# esp-module-su.net
KiCad netlist of a schematic drawn in EAGLE
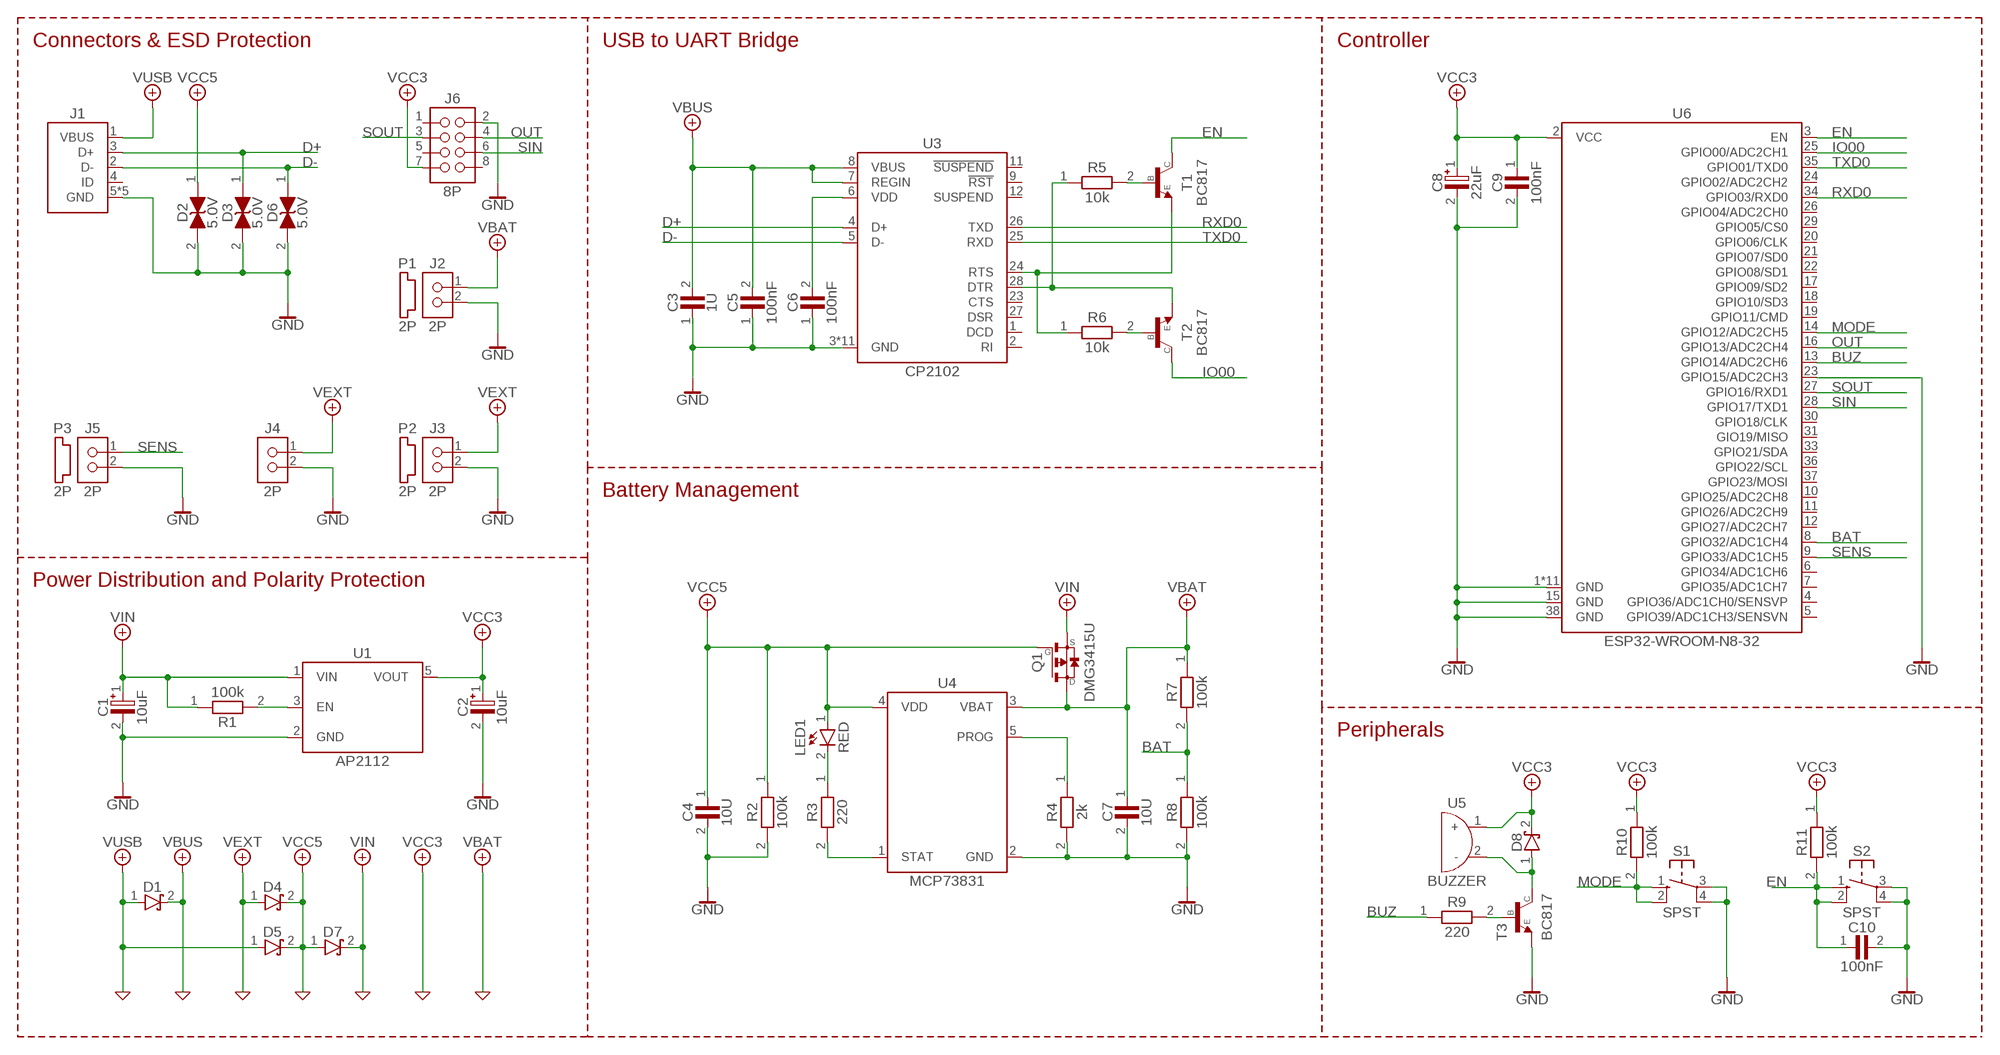
[diagram p0: schematic, sheet 1]

(export (version "E")
  (design (tool "Eeschema 10.0.6"))
  (components
    (comp (ref "C1")
      (value "10uF")
      (footprint "eagle-import:I1206-M3216-D")
      (fields
        (field (name "MF") "Kyocera AVX")
        (field (name "MPN") "TAJA106K016RNJ")
        (field (name "VOLTAGE") "16V")
      )
      (libsource (lib "eagle-import") (part "CAPACITOR-TANTALUM-I1206-M3216-10U"))
    )
    (comp (ref "C2")
      (value "10uF")
      (footprint "eagle-import:I1206-M3216-D")
      (fields
        (field (name "MF") "Kyocera AVX")
        (field (name "MPN") "TAJA106K016RNJ")
        (field (name "VOLTAGE") "16V")
      )
      (libsource (lib "eagle-import") (part "CAPACITOR-TANTALUM-I1206-M3216-10U"))
    )
    (comp (ref "C3")
      (value "1U")
      (footprint "eagle-import:I0805-M2012-C")
      (fields
        (field (name "MF") " FH (Guangdong Fenghua Advanced Tech)")
        (field (name "MPN") "0805B105K500NT")
        (field (name "TOLERANCE") "10%")
      )
      (libsource (lib "eagle-import") (part "CAPACITOR-CERAMIC-I0805-M2012-1U"))
    )
    (comp (ref "C4")
      (value "10U")
      (footprint "eagle-import:I0805-M2012-C")
      (fields
        (field (name "MF") "Samsung Electro-Mechanics")
        (field (name "MPN") "CL21A106KAYNNNE")
        (field (name "TOLERANCE") "10%")
      )
      (libsource (lib "eagle-import") (part "CAPACITOR-CERAMIC-I0805-M2012-10U"))
    )
    (comp (ref "C5")
      (value "100nF")
      (footprint "eagle-import:I0805-M2012-C")
      (fields
        (field (name "MF") "FH (Guangdong Fenghua Advanced Tech)")
        (field (name "MPN") "0805B104K500NT")
        (field (name "TOLERANCE") "10%")
      )
      (libsource (lib "eagle-import") (part "CAPACITOR-CERAMIC-I0805-M2012-100N"))
    )
    (comp (ref "C6")
      (value "100nF")
      (footprint "eagle-import:I0805-M2012-C")
      (fields
        (field (name "MF") "FH (Guangdong Fenghua Advanced Tech)")
        (field (name "MPN") "0805B104K500NT")
        (field (name "TOLERANCE") "10%")
      )
      (libsource (lib "eagle-import") (part "CAPACITOR-CERAMIC-I0805-M2012-100N"))
    )
    (comp (ref "C7")
      (value "10U")
      (footprint "eagle-import:I0805-M2012-C")
      (fields
        (field (name "MF") "Samsung Electro-Mechanics")
        (field (name "MPN") "CL21A106KAYNNNE")
        (field (name "TOLERANCE") "10%")
      )
      (libsource (lib "eagle-import") (part "CAPACITOR-CERAMIC-I0805-M2012-10U"))
    )
    (comp (ref "C8")
      (value "22uF")
      (footprint "eagle-import:I1206-M3216-D")
      (fields
        (field (name "MF") "Kyocera AVX")
        (field (name "MPN") "TAJA226K010RNJ")
        (field (name "VOLTAGE") "10V")
      )
      (libsource (lib "eagle-import") (part "CAPACITOR-TANTALUM-I1206-M3216-22U"))
    )
    (comp (ref "C9")
      (value "100nF")
      (footprint "eagle-import:I0805-M2012-C")
      (fields
        (field (name "MF") "FH (Guangdong Fenghua Advanced Tech)")
        (field (name "MPN") "0805B104K500NT")
        (field (name "TOLERANCE") "10%")
      )
      (libsource (lib "eagle-import") (part "CAPACITOR-CERAMIC-I0805-M2012-100N"))
    )
    (comp (ref "C10")
      (value "100nF")
      (footprint "eagle-import:I0805-M2012-C")
      (fields
        (field (name "MF") "FH (Guangdong Fenghua Advanced Tech)")
        (field (name "MPN") "0805B104K500NT")
        (field (name "TOLERANCE") "10%")
      )
      (libsource (lib "eagle-import") (part "CAPACITOR-CERAMIC-I0805-M2012-100N"))
    )
    (comp (ref "D1")
      (value "30V")
      (footprint "eagle-import:SOD-323")
      (fields (field (name "MF") "Diodes Incorporated") (field (name "MPN") "BAT760-7"))
      (libsource (lib "eagle-import") (part "SCHOTTKY-SOD-323-30V"))
    )
    (comp (ref "D2")
      (value "5.0V")
      (footprint "eagle-import:SOD-523")
      (fields (field (name "MF") " LRC") (field (name "MPN") "LESD5D5.0CT1G"))
      (libsource (lib "eagle-import") (part "ZENER-BI-SOD-523-5.0V"))
    )
    (comp (ref "D3")
      (value "5.0V")
      (footprint "eagle-import:SOD-523")
      (fields (field (name "MF") " LRC") (field (name "MPN") "LESD5D5.0CT1G"))
      (libsource (lib "eagle-import") (part "ZENER-BI-SOD-523-5.0V"))
    )
    (comp (ref "D4")
      (value "30V")
      (footprint "eagle-import:SOD-323")
      (fields (field (name "MF") "Diodes Incorporated") (field (name "MPN") "BAT760-7"))
      (libsource (lib "eagle-import") (part "SCHOTTKY-SOD-323-30V"))
    )
    (comp (ref "D5")
      (value "30V")
      (footprint "eagle-import:SOD-323")
      (fields (field (name "MF") "Diodes Incorporated") (field (name "MPN") "BAT760-7"))
      (libsource (lib "eagle-import") (part "SCHOTTKY-SOD-323-30V"))
    )
    (comp (ref "D6")
      (value "5.0V")
      (footprint "eagle-import:SOD-523")
      (fields (field (name "MF") " LRC") (field (name "MPN") "LESD5D5.0CT1G"))
      (libsource (lib "eagle-import") (part "ZENER-BI-SOD-523-5.0V"))
    )
    (comp (ref "D7")
      (value "30V")
      (footprint "eagle-import:SOD-323")
      (fields (field (name "MF") "Diodes Incorporated") (field (name "MPN") "BAT760-7"))
      (libsource (lib "eagle-import") (part "SCHOTTKY-SOD-323-30V"))
    )
    (comp (ref "D8")
      (value "30V")
      (footprint "eagle-import:SOD-323")
      (fields (field (name "MF") "Diodes Incorporated") (field (name "MPN") "BAT760-7"))
      (libsource (lib "eagle-import") (part "SCHOTTKY-SOD-323-30V"))
    )
    (comp (ref "J1")
      (value "USB-A-MICRO-SMD-SIDE")
      (footprint "eagle-import:USB-A-MICRO-SMD-SIDE")
      (fields (field (name "MF") "XKB Connectivity") (field (name "MPN") "U254-051T-4BHJ25-F2S"))
      (libsource (lib "eagle-import") (part "USB-A-MICRO-SMD-SIDE"))
    )
    (comp (ref "J2")
      (value "2P")
      (footprint "eagle-import:JST-S2B-PH-SM4-TB")
      (fields (field (name "MF") "JST Sales America") (field (name "MPN") "S2B-PH-SM4-TB(LF)(SN)"))
      (libsource (lib "eagle-import") (part "HEADER-02P-1R-S2B-PH-SM4-TB"))
    )
    (comp (ref "J3")
      (value "2P")
      (footprint "eagle-import:JST-S2B-PH-SM4-TB")
      (fields (field (name "MF") "JST Sales America") (field (name "MPN") "S2B-PH-SM4-TB(LF)(SN)"))
      (libsource (lib "eagle-import") (part "HEADER-02P-1R-S2B-PH-SM4-TB"))
    )
    (comp (ref "J4")
      (value "2P")
      (footprint "eagle-import:PZ254V-11-02P")
      (fields (field (name "MF") " XFCN") (field (name "MPN") " PZ254V-11-02P"))
      (libsource (lib "eagle-import") (part "HEADER-02P-1R-PZ254V-11-02P"))
    )
    (comp (ref "J5")
      (value "2P")
      (footprint "eagle-import:JST-S2B-PH-SM4-TB")
      (fields (field (name "MF") "JST Sales America") (field (name "MPN") "S2B-PH-SM4-TB(LF)(SN)"))
      (libsource (lib "eagle-import") (part "HEADER-02P-1R-S2B-PH-SM4-TB"))
    )
    (comp (ref "J6")
      (value "8P")
      (footprint "eagle-import:PM254V-12-08-H85")
      (fields (field (name "MF") "XFCN") (field (name "MPN") "PM254V-12-08-H85"))
      (libsource (lib "eagle-import") (part "HEADER-08P-2R-PM254V-12-08-H85"))
    )
    (comp (ref "LED1")
      (value "RED")
      (footprint "eagle-import:I0805-M2012-D")
      (fields (field (name "MF") "Foshan NationStar Optoelectronics") (field (name "MPN") "FC-2012HRK-620D"))
      (libsource (lib "eagle-import") (part "LED-I0805-M2012-RED"))
    )
    (comp (ref "P1")
      (value "2P")
      (footprint "eagle-import:CONNECTOR-DEFAULT")
      (fields (field (name "MF") "JST Sales America") (field (name "MPN") "PHR-2"))
      (libsource (lib "eagle-import") (part "CONNECTOR-02P-1R-PHR"))
    )
    (comp (ref "P2")
      (value "2P")
      (footprint "eagle-import:CONNECTOR-DEFAULT")
      (fields (field (name "MF") "JST Sales America") (field (name "MPN") "PHR-2"))
      (libsource (lib "eagle-import") (part "CONNECTOR-02P-1R-PHR"))
    )
    (comp (ref "P3")
      (value "2P")
      (footprint "eagle-import:CONNECTOR-DEFAULT")
      (fields (field (name "MF") "JST Sales America") (field (name "MPN") "PHR-2"))
      (libsource (lib "eagle-import") (part "CONNECTOR-02P-1R-PHR"))
    )
    (comp (ref "Q1")
      (value "DMG3415U")
      (footprint "eagle-import:SOT-23-3")
      (fields
        (field (name "MF") "Diodes Incorporated")
        (field (name "MPN") "DMG3415U-7")
        (field (name "VOLTAGE") "20V")
      )
      (libsource (lib "eagle-import") (part "MOSFET-P-CHANNEL-SOT-23-3-20V-4A"))
    )
    (comp (ref "R1")
      (value "100k")
      (footprint "eagle-import:I0805-M2012-R")
      (fields (field (name "MF") "UNI-ROYAL(Uniroyal Elec)") (field (name "MPN") "0805W8F1003T5E"))
      (libsource (lib "eagle-import") (part "RESISTOR-I0805-M2012-100K"))
    )
    (comp (ref "R2")
      (value "100k")
      (footprint "eagle-import:I0805-M2012-R")
      (fields (field (name "MF") "UNI-ROYAL(Uniroyal Elec)") (field (name "MPN") "0805W8F1003T5E"))
      (libsource (lib "eagle-import") (part "RESISTOR-I0805-M2012-100K"))
    )
    (comp (ref "R3")
      (value "220")
      (footprint "eagle-import:I0805-M2012-R")
      (fields (field (name "MF") "UNI-ROYAL(Uniroyal Elec)") (field (name "MPN") "0805W8F2200T5E"))
      (libsource (lib "eagle-import") (part "RESISTOR-I0805-M2012-220"))
    )
    (comp (ref "R4")
      (value "2k")
      (footprint "eagle-import:I0805-M2012-R")
      (fields (field (name "MF") "UNI-ROYAL(Uniroyal Elec)") (field (name "MPN") "0805W8F2001T5E"))
      (libsource (lib "eagle-import") (part "RESISTOR-I0805-M2012-2K"))
    )
    (comp (ref "R5")
      (value "10k")
      (footprint "eagle-import:I0805-M2012-R")
      (fields (field (name "MF") " UNI-ROYAL(Uniroyal Elec)") (field (name "MPN") "0805W8F1002T5E"))
      (libsource (lib "eagle-import") (part "RESISTOR-I0805-M2012-10K"))
    )
    (comp (ref "R6")
      (value "10k")
      (footprint "eagle-import:I0805-M2012-R")
      (fields (field (name "MF") " UNI-ROYAL(Uniroyal Elec)") (field (name "MPN") "0805W8F1002T5E"))
      (libsource (lib "eagle-import") (part "RESISTOR-I0805-M2012-10K"))
    )
    (comp (ref "R7")
      (value "100k")
      (footprint "eagle-import:I0805-M2012-R")
      (fields (field (name "MF") "UNI-ROYAL(Uniroyal Elec)") (field (name "MPN") "0805W8F1003T5E"))
      (libsource (lib "eagle-import") (part "RESISTOR-I0805-M2012-100K"))
    )
    (comp (ref "R8")
      (value "100k")
      (footprint "eagle-import:I0805-M2012-R")
      (fields (field (name "MF") "UNI-ROYAL(Uniroyal Elec)") (field (name "MPN") "0805W8F1003T5E"))
      (libsource (lib "eagle-import") (part "RESISTOR-I0805-M2012-100K"))
    )
    (comp (ref "R9")
      (value "220")
      (footprint "eagle-import:I0805-M2012-R")
      (fields (field (name "MF") "UNI-ROYAL(Uniroyal Elec)") (field (name "MPN") "0805W8F2200T5E"))
      (libsource (lib "eagle-import") (part "RESISTOR-I0805-M2012-220"))
    )
    (comp (ref "R10")
      (value "100k")
      (footprint "eagle-import:I0805-M2012-R")
      (fields (field (name "MF") "UNI-ROYAL(Uniroyal Elec)") (field (name "MPN") "0805W8F1003T5E"))
      (libsource (lib "eagle-import") (part "RESISTOR-I0805-M2012-100K"))
    )
    (comp (ref "R11")
      (value "100k")
      (footprint "eagle-import:I0805-M2012-R")
      (fields (field (name "MF") "UNI-ROYAL(Uniroyal Elec)") (field (name "MPN") "0805W8F1003T5E"))
      (libsource (lib "eagle-import") (part "RESISTOR-I0805-M2012-100K"))
    )
    (comp (ref "S1")
      (value "SPST")
      (footprint "eagle-import:SMD-SW-4")
      (fields
        (field (name "MF") "XKB Enterprise")
        (field (name "MPN") "TS-1187A-B-A-B")
        (field (name "VOLTAGE") "12V")
      )
      (libsource (lib "eagle-import") (part "SWITCH-12V-50MA"))
    )
    (comp (ref "S2")
      (value "SPST")
      (footprint "eagle-import:SMD-SW-4")
      (fields
        (field (name "MF") "XKB Enterprise")
        (field (name "MPN") "TS-1187A-B-A-B")
        (field (name "VOLTAGE") "12V")
      )
      (libsource (lib "eagle-import") (part "SWITCH-12V-50MA"))
    )
    (comp (ref "T1")
      (value "BC817")
      (footprint "eagle-import:SOT-23-3")
      (fields (field (name "MF") " Nexperia") (field (name "MPN") " BC817-40,215"))
      (libsource (lib "eagle-import") (part "TRANSISTOR-NPN-SOT-23-3"))
    )
    (comp (ref "T2")
      (value "BC817")
      (footprint "eagle-import:SOT-23-3")
      (fields (field (name "MF") " Nexperia") (field (name "MPN") " BC817-40,215"))
      (libsource (lib "eagle-import") (part "TRANSISTOR-NPN-SOT-23-3"))
    )
    (comp (ref "T3")
      (value "BC817")
      (footprint "eagle-import:SOT-23-3")
      (fields (field (name "MF") " Nexperia") (field (name "MPN") " BC817-40,215"))
      (libsource (lib "eagle-import") (part "TRANSISTOR-NPN-SOT-23-3"))
    )
    (comp (ref "U1")
      (value "AP2112")
      (footprint "eagle-import:SOT-25-5")
      (fields (field (name "MF") "TECH PUBLIC") (field (name "MPN") "TPAP2112K-3.3TRG1"))
      (libsource (lib "eagle-import") (part "AP2112-SOT-25-5"))
    )
    (comp (ref "U3")
      (value "CP2102")
      (footprint "eagle-import:QFN-28")
      (fields (field (name "MF") "SILICON LABS") (field (name "MPN") "CP2102-GMR"))
      (libsource (lib "eagle-import") (part "CP2102-QFN-28"))
    )
    (comp (ref "U4")
      (value "MCP73831")
      (footprint "eagle-import:SOT-23-5")
      (fields (field (name "MF") "Microchip Tech") (field (name "MPN") "MCP73831T-2ATI/OT"))
      (libsource (lib "eagle-import") (part "MCP73831-SOT-23-5"))
    )
    (comp (ref "U5")
      (value "BUZZER")
      (footprint "eagle-import:SMD-BUZZER")
      (fields (field (name "MF") "MLT-7525") (field (name "MPN") "Jiangsu Huaneng Elec"))
      (libsource (lib "eagle-import") (part "BUZZER"))
    )
    (comp (ref "U6")
      (value "ESP32-WROOM-N8-32")
      (footprint "eagle-import:ESP32-WROOM-32")
      (fields (field (name "MF") "Espressif Systems") (field (name "MPN") " ESP32-WROOM-32-N8"))
      (libsource (lib "eagle-import") (part "ESP32-WROOM-32-N8"))
    )
  )
  (nets
    (net (code "1") (name "/BAT") (class "Default")
      (node (ref "R7") (pin "2") (pinfunction "2_2") (pintype "passive"))
      (node (ref "R8") (pin "1") (pinfunction "1_1") (pintype "passive"))
      (node (ref "U6") (pin "8") (pinfunction "GPIO32/ADC1CH4_8") (pintype "bidirectional"))
    )
    (net (code "2") (name "/BUZ") (class "Default")
      (node (ref "R9") (pin "1") (pinfunction "1_1") (pintype "passive"))
      (node (ref "U6") (pin "13") (pinfunction "GPIO14/ADC2CH6_13") (pintype "bidirectional"))
    )
    (net (code "3") (name "/D+") (class "Default")
      (node (ref "D3") (pin "1") (pinfunction "A_1") (pintype "passive"))
      (node (ref "J1") (pin "3") (pinfunction "D+_3") (pintype "bidirectional"))
      (node (ref "U3") (pin "4") (pinfunction "D+_4") (pintype "bidirectional"))
    )
    (net (code "4") (name "/D-") (class "Default")
      (node (ref "D6") (pin "1") (pinfunction "A_1") (pintype "passive"))
      (node (ref "J1") (pin "2") (pinfunction "D-_2") (pintype "bidirectional"))
      (node (ref "U3") (pin "5") (pinfunction "D-_5") (pintype "bidirectional"))
    )
    (net (code "5") (name "/EN") (class "Default")
      (node (ref "C10") (pin "1") (pinfunction "1_1") (pintype "passive"))
      (node (ref "R11") (pin "2") (pinfunction "2_2") (pintype "passive"))
      (node (ref "S2") (pin "1") (pinfunction "1_1") (pintype "bidirectional"))
      (node (ref "S2") (pin "2") (pinfunction "2_2") (pintype "bidirectional"))
      (node (ref "T1") (pin "3") (pinfunction "C_3") (pintype "passive"))
      (node (ref "U6") (pin "3") (pinfunction "EN_3") (pintype "bidirectional"))
    )
    (net (code "6") (name "/IO00") (class "Default")
      (node (ref "T2") (pin "3") (pinfunction "C_3") (pintype "passive"))
      (node (ref "U6") (pin "25") (pinfunction "GPIO00/ADC2CH1_25") (pintype "bidirectional"))
    )
    (net (code "7") (name "/MODE") (class "Default")
      (node (ref "R10") (pin "2") (pinfunction "2_2") (pintype "passive"))
      (node (ref "S1") (pin "1") (pinfunction "1_1") (pintype "bidirectional"))
      (node (ref "S1") (pin "2") (pinfunction "2_2") (pintype "bidirectional"))
      (node (ref "U6") (pin "14") (pinfunction "GPIO12/ADC2CH5_14") (pintype "bidirectional"))
    )
    (net (code "8") (name "/OUT") (class "Default")
      (node (ref "J6") (pin "4") (pinfunction "04_4") (pintype "passive"))
      (node (ref "U6") (pin "16") (pinfunction "GPIO13/ADC2CH4_16") (pintype "bidirectional"))
    )
    (net (code "9") (name "/RXD0") (class "Default")
      (node (ref "U3") (pin "26") (pinfunction "TXD_26") (pintype "bidirectional"))
      (node (ref "U6") (pin "34") (pinfunction "GPIO03/RXD0_34") (pintype "bidirectional"))
    )
    (net (code "10") (name "/SENS") (class "Default")
      (node (ref "J5") (pin "1") (pinfunction "01_1") (pintype "passive"))
      (node (ref "U6") (pin "9") (pinfunction "GPIO33/ADC1CH5_9") (pintype "bidirectional"))
    )
    (net (code "11") (name "/SIN") (class "Default")
      (node (ref "J6") (pin "6") (pinfunction "06_6") (pintype "passive"))
      (node (ref "U6") (pin "28") (pinfunction "GPIO17/TXD1_28") (pintype "bidirectional"))
    )
    (net (code "12") (name "/SOUT") (class "Default")
      (node (ref "J6") (pin "3") (pinfunction "03_3") (pintype "passive"))
      (node (ref "U6") (pin "27") (pinfunction "GPIO16/RXD1_27") (pintype "bidirectional"))
    )
    (net (code "13") (name "/TXD0") (class "Default")
      (node (ref "U3") (pin "25") (pinfunction "RXD_25") (pintype "bidirectional"))
      (node (ref "U6") (pin "35") (pinfunction "GPIO01/TXD0_35") (pintype "bidirectional"))
    )
    (net (code "14") (name "GND") (class "Default")
      (node (ref "C1") (pin "2") (pinfunction "-_2") (pintype "passive"))
      (node (ref "C10") (pin "2") (pinfunction "2_2") (pintype "passive"))
      (node (ref "C2") (pin "2") (pinfunction "-_2") (pintype "passive"))
      (node (ref "C3") (pin "1") (pinfunction "1_1") (pintype "passive"))
      (node (ref "C4") (pin "2") (pinfunction "2_2") (pintype "passive"))
      (node (ref "C5") (pin "1") (pinfunction "1_1") (pintype "passive"))
      (node (ref "C6") (pin "1") (pinfunction "1_1") (pintype "passive"))
      (node (ref "C7") (pin "2") (pinfunction "2_2") (pintype "passive"))
      (node (ref "C8") (pin "2") (pinfunction "-_2") (pintype "passive"))
      (node (ref "C9") (pin "2") (pinfunction "2_2") (pintype "passive"))
      (node (ref "D2") (pin "2") (pinfunction "C_2") (pintype "passive"))
      (node (ref "D3") (pin "2") (pinfunction "C_2") (pintype "passive"))
      (node (ref "D6") (pin "2") (pinfunction "C_2") (pintype "passive"))
      (node (ref "J1") (pin "5") (pinfunction "GND_5") (pintype "power_in"))
      (node (ref "J1") (pin "6") (pinfunction "GND_6") (pintype "power_in"))
      (node (ref "J1") (pin "7") (pinfunction "GND_7") (pintype "power_in"))
      (node (ref "J1") (pin "8") (pinfunction "GND_8") (pintype "power_in"))
      (node (ref "J1") (pin "9") (pinfunction "GND_9") (pintype "power_in"))
      (node (ref "J2") (pin "2") (pinfunction "02_2") (pintype "passive"))
      (node (ref "J3") (pin "2") (pinfunction "02_2") (pintype "passive"))
      (node (ref "J4") (pin "2") (pinfunction "02_2") (pintype "passive"))
      (node (ref "J5") (pin "2") (pinfunction "02_2") (pintype "passive"))
      (node (ref "J6") (pin "2") (pinfunction "02_2") (pintype "passive"))
      (node (ref "R2") (pin "2") (pinfunction "2_2") (pintype "passive"))
      (node (ref "R4") (pin "2") (pinfunction "2_2") (pintype "passive"))
      (node (ref "R8") (pin "2") (pinfunction "2_2") (pintype "passive"))
      (node (ref "S1") (pin "3") (pinfunction "3_3") (pintype "bidirectional"))
      (node (ref "S1") (pin "4") (pinfunction "4_4") (pintype "bidirectional"))
      (node (ref "S2") (pin "3") (pinfunction "3_3") (pintype "bidirectional"))
      (node (ref "S2") (pin "4") (pinfunction "4_4") (pintype "bidirectional"))
      (node (ref "T3") (pin "2") (pinfunction "E_2") (pintype "passive"))
      (node (ref "U1") (pin "2") (pinfunction "GND_2") (pintype "power_in"))
      (node (ref "U3") (pin "29") (pinfunction "GND_29") (pintype "power_in"))
      (node (ref "U3") (pin "3") (pinfunction "GND_3") (pintype "power_in"))
      (node (ref "U3") (pin "30") (pinfunction "GND_30") (pintype "power_in"))
      (node (ref "U3") (pin "31") (pinfunction "GND_31") (pintype "power_in"))
      (node (ref "U3") (pin "32") (pinfunction "GND_32") (pintype "power_in"))
      (node (ref "U3") (pin "33") (pinfunction "GND_33") (pintype "power_in"))
      (node (ref "U3") (pin "34") (pinfunction "GND_34") (pintype "power_in"))
      (node (ref "U3") (pin "35") (pinfunction "GND_35") (pintype "power_in"))
      (node (ref "U3") (pin "36") (pinfunction "GND_36") (pintype "power_in"))
      (node (ref "U3") (pin "37") (pinfunction "GND_37") (pintype "power_in"))
      (node (ref "U3") (pin "38") (pinfunction "GND_38") (pintype "power_in"))
      (node (ref "U4") (pin "2") (pinfunction "GND_2") (pintype "power_in"))
      (node (ref "U6") (pin "1") (pinfunction "GND_1") (pintype "power_in"))
      (node (ref "U6") (pin "15") (pinfunction "GND_15") (pintype "power_in"))
      (node (ref "U6") (pin "23") (pinfunction "GPIO15/ADC2CH3_23") (pintype "bidirectional"))
      (node (ref "U6") (pin "38") (pinfunction "GND_38") (pintype "bidirectional"))
      (node (ref "U6") (pin "39") (pinfunction "GND_39") (pintype "power_in"))
      (node (ref "U6") (pin "40") (pinfunction "GND_40") (pintype "power_in"))
      (node (ref "U6") (pin "41") (pinfunction "GND_41") (pintype "power_in"))
      (node (ref "U6") (pin "42") (pinfunction "GND_42") (pintype "power_in"))
      (node (ref "U6") (pin "43") (pinfunction "GND_43") (pintype "power_in"))
      (node (ref "U6") (pin "44") (pinfunction "GND_44") (pintype "power_in"))
      (node (ref "U6") (pin "45") (pinfunction "GND_45") (pintype "power_in"))
      (node (ref "U6") (pin "46") (pinfunction "GND_46") (pintype "power_in"))
      (node (ref "U6") (pin "47") (pinfunction "GND_47") (pintype "power_in"))
      (node (ref "U6") (pin "48") (pinfunction "GND_48") (pintype "power_in"))
    )
    (net (code "15") (name "Net-(D8-A)") (class "Default")
      (node (ref "D8") (pin "1") (pinfunction "A_1") (pintype "passive"))
      (node (ref "T3") (pin "3") (pinfunction "C_3") (pintype "passive"))
      (node (ref "U5") (pin "2") (pinfunction "-_2") (pintype "bidirectional"))
    )
    (net (code "16") (name "Net-(LED1-C)") (class "Default")
      (node (ref "LED1") (pin "2") (pinfunction "C_2") (pintype "passive"))
      (node (ref "R3") (pin "1") (pinfunction "1_1") (pintype "passive"))
    )
    (net (code "17") (name "Net-(T1-B)") (class "Default")
      (node (ref "R5") (pin "2") (pinfunction "2_2") (pintype "passive"))
      (node (ref "T1") (pin "1") (pinfunction "B_1") (pintype "passive"))
    )
    (net (code "18") (name "Net-(T1-E)") (class "Default")
      (node (ref "R6") (pin "1") (pinfunction "1_1") (pintype "passive"))
      (node (ref "T1") (pin "2") (pinfunction "E_2") (pintype "passive"))
      (node (ref "U3") (pin "24") (pinfunction "RTS_24") (pintype "bidirectional"))
    )
    (net (code "19") (name "Net-(T2-B)") (class "Default")
      (node (ref "R6") (pin "2") (pinfunction "2_2") (pintype "passive"))
      (node (ref "T2") (pin "1") (pinfunction "B_1") (pintype "passive"))
    )
    (net (code "20") (name "Net-(T2-E)") (class "Default")
      (node (ref "R5") (pin "1") (pinfunction "1_1") (pintype "passive"))
      (node (ref "T2") (pin "2") (pinfunction "E_2") (pintype "passive"))
      (node (ref "U3") (pin "28") (pinfunction "DTR_28") (pintype "bidirectional"))
    )
    (net (code "21") (name "Net-(T3-B)") (class "Default")
      (node (ref "R9") (pin "2") (pinfunction "2_2") (pintype "passive"))
      (node (ref "T3") (pin "1") (pinfunction "B_1") (pintype "passive"))
    )
    (net (code "22") (name "Net-(U1-EN)") (class "Default")
      (node (ref "R1") (pin "2") (pinfunction "2_2") (pintype "passive"))
      (node (ref "U1") (pin "3") (pinfunction "EN_3") (pintype "bidirectional"))
    )
    (net (code "23") (name "Net-(U3-VDD)") (class "Default")
      (node (ref "C6") (pin "2") (pinfunction "2_2") (pintype "passive"))
      (node (ref "U3") (pin "6") (pinfunction "VDD_6") (pintype "power_in"))
    )
    (net (code "24") (name "Net-(U4-PROG)") (class "Default")
      (node (ref "R4") (pin "1") (pinfunction "1_1") (pintype "passive"))
      (node (ref "U4") (pin "5") (pinfunction "PROG_5") (pintype "bidirectional"))
    )
    (net (code "25") (name "Net-(U4-STAT)") (class "Default")
      (node (ref "R3") (pin "2") (pinfunction "2_2") (pintype "passive"))
      (node (ref "U4") (pin "1") (pinfunction "STAT_1") (pintype "bidirectional"))
    )
    (net (code "26") (name "VBAT") (class "Default")
      (node (ref "C7") (pin "1") (pinfunction "1_1") (pintype "passive"))
      (node (ref "J2") (pin "1") (pinfunction "01_1") (pintype "passive"))
      (node (ref "Q1") (pin "3") (pinfunction "D_3") (pintype "passive"))
      (node (ref "R7") (pin "1") (pinfunction "1_1") (pintype "passive"))
      (node (ref "U4") (pin "3") (pinfunction "VBAT_3") (pintype "bidirectional"))
    )
    (net (code "27") (name "VBUS") (class "Default")
      (node (ref "C3") (pin "2") (pinfunction "2_2") (pintype "passive"))
      (node (ref "C5") (pin "2") (pinfunction "2_2") (pintype "passive"))
      (node (ref "D1") (pin "2") (pinfunction "C_2") (pintype "passive"))
      (node (ref "U3") (pin "7") (pinfunction "REGIN_7") (pintype "bidirectional"))
      (node (ref "U3") (pin "8") (pinfunction "VBUS_8") (pintype "bidirectional"))
    )
    (net (code "28") (name "VCC3") (class "Default")
      (node (ref "C2") (pin "1") (pinfunction "+_1") (pintype "passive"))
      (node (ref "C8") (pin "1") (pinfunction "+_1") (pintype "passive"))
      (node (ref "C9") (pin "1") (pinfunction "1_1") (pintype "passive"))
      (node (ref "D8") (pin "2") (pinfunction "C_2") (pintype "passive"))
      (node (ref "J6") (pin "7") (pinfunction "07_7") (pintype "passive"))
      (node (ref "R10") (pin "1") (pinfunction "1_1") (pintype "passive"))
      (node (ref "R11") (pin "1") (pinfunction "1_1") (pintype "passive"))
      (node (ref "U1") (pin "5") (pinfunction "VOUT_5") (pintype "power_in"))
      (node (ref "U5") (pin "1") (pinfunction "+_1") (pintype "bidirectional"))
      (node (ref "U6") (pin "2") (pinfunction "VCC_2") (pintype "power_in"))
    )
    (net (code "29") (name "VCC5") (class "Default")
      (node (ref "C4") (pin "1") (pinfunction "1_1") (pintype "passive"))
      (node (ref "D2") (pin "1") (pinfunction "A_1") (pintype "passive"))
      (node (ref "D4") (pin "2") (pinfunction "C_2") (pintype "passive"))
      (node (ref "D5") (pin "2") (pinfunction "C_2") (pintype "passive"))
      (node (ref "D7") (pin "1") (pinfunction "A_1") (pintype "passive"))
      (node (ref "LED1") (pin "1") (pinfunction "A_1") (pintype "passive"))
      (node (ref "Q1") (pin "1") (pinfunction "G_1") (pintype "passive"))
      (node (ref "R2") (pin "1") (pinfunction "1_1") (pintype "passive"))
      (node (ref "U4") (pin "4") (pinfunction "VDD_4") (pintype "power_in"))
    )
    (net (code "30") (name "VEXT") (class "Default")
      (node (ref "D4") (pin "1") (pinfunction "A_1") (pintype "passive"))
      (node (ref "J3") (pin "1") (pinfunction "01_1") (pintype "passive"))
      (node (ref "J4") (pin "1") (pinfunction "01_1") (pintype "passive"))
    )
    (net (code "31") (name "VIN") (class "Default")
      (node (ref "C1") (pin "1") (pinfunction "+_1") (pintype "passive"))
      (node (ref "D7") (pin "2") (pinfunction "C_2") (pintype "passive"))
      (node (ref "Q1") (pin "2") (pinfunction "S_2") (pintype "passive"))
      (node (ref "R1") (pin "1") (pinfunction "1_1") (pintype "passive"))
      (node (ref "U1") (pin "1") (pinfunction "VIN_1") (pintype "power_in"))
    )
    (net (code "32") (name "VUSB") (class "Default")
      (node (ref "D1") (pin "1") (pinfunction "A_1") (pintype "passive"))
      (node (ref "D5") (pin "1") (pinfunction "A_1") (pintype "passive"))
      (node (ref "J1") (pin "1") (pinfunction "VBUS_1") (pintype "power_in"))
    )
    (net (code "33") (name "unconnected-(J1-ID-Pad4)") (class "Default")
      (node (ref "J1") (pin "4") (pinfunction "ID_4") (pintype "passive"))
    )
    (net (code "34") (name "unconnected-(J6-01-Pad1)") (class "Default")
      (node (ref "J6") (pin "1") (pinfunction "01_1") (pintype "passive"))
    )
    (net (code "35") (name "unconnected-(J6-05-Pad5)") (class "Default")
      (node (ref "J6") (pin "5") (pinfunction "05_5") (pintype "passive"))
    )
    (net (code "36") (name "unconnected-(J6-08-Pad8)") (class "Default")
      (node (ref "J6") (pin "8") (pinfunction "08_8") (pintype "passive"))
    )
    (net (code "37") (name "unconnected-(U3-CTS-Pad23)") (class "Default")
      (node (ref "U3") (pin "23") (pinfunction "CTS_23") (pintype "bidirectional"))
    )
    (net (code "38") (name "unconnected-(U3-DCD-Pad1)") (class "Default")
      (node (ref "U3") (pin "1") (pinfunction "DCD_1") (pintype "bidirectional"))
    )
    (net (code "39") (name "unconnected-(U3-DSR-Pad27)") (class "Default")
      (node (ref "U3") (pin "27") (pinfunction "DSR_27") (pintype "bidirectional"))
    )
    (net (code "40") (name "unconnected-(U3-RI-Pad2)") (class "Default")
      (node (ref "U3") (pin "2") (pinfunction "RI_2") (pintype "bidirectional"))
    )
    (net (code "41") (name "unconnected-(U3-SUSPEND-Pad12)") (class "Default")
      (node (ref "U3") (pin "12") (pinfunction "SUSPEND_12") (pintype "bidirectional"))
    )
    (net (code "42") (name "unconnected-(U3-~{RST}-Pad9)") (class "Default")
      (node (ref "U3") (pin "9") (pinfunction "~{RST}_9") (pintype "bidirectional"))
    )
    (net (code "43") (name "unconnected-(U3-~{SUSPEND}-Pad11)") (class "Default")
      (node (ref "U3") (pin "11") (pinfunction "~{SUSPEND}_11") (pintype "bidirectional"))
    )
    (net (code "44") (name "unconnected-(U6-GIO19{slash}MISO-Pad31)") (class "Default")
      (node (ref "U6") (pin "31") (pinfunction "GIO19/MISO_31") (pintype "bidirectional"))
    )
    (net (code "45") (name "unconnected-(U6-GPIO02{slash}ADC2CH2-Pad24)") (class "Default")
      (node (ref "U6") (pin "24") (pinfunction "GPIO02/ADC2CH2_24") (pintype "bidirectional"))
    )
    (net (code "46") (name "unconnected-(U6-GPIO04{slash}ADC2CH0-Pad26)") (class "Default")
      (node (ref "U6") (pin "26") (pinfunction "GPIO04/ADC2CH0_26") (pintype "bidirectional"))
    )
    (net (code "47") (name "unconnected-(U6-GPIO05{slash}CS0-Pad29)") (class "Default")
      (node (ref "U6") (pin "29") (pinfunction "GPIO05/CS0_29") (pintype "bidirectional"))
    )
    (net (code "48") (name "unconnected-(U6-GPIO06{slash}CLK-Pad20)") (class "Default")
      (node (ref "U6") (pin "20") (pinfunction "GPIO06/CLK_20") (pintype "bidirectional"))
    )
    (net (code "49") (name "unconnected-(U6-GPIO07{slash}SD0-Pad21)") (class "Default")
      (node (ref "U6") (pin "21") (pinfunction "GPIO07/SD0_21") (pintype "bidirectional"))
    )
    (net (code "50") (name "unconnected-(U6-GPIO08{slash}SD1-Pad22)") (class "Default")
      (node (ref "U6") (pin "22") (pinfunction "GPIO08/SD1_22") (pintype "bidirectional"))
    )
    (net (code "51") (name "unconnected-(U6-GPIO09{slash}SD2-Pad17)") (class "Default")
      (node (ref "U6") (pin "17") (pinfunction "GPIO09/SD2_17") (pintype "bidirectional"))
    )
    (net (code "52") (name "unconnected-(U6-GPIO10{slash}SD3-Pad18)") (class "Default")
      (node (ref "U6") (pin "18") (pinfunction "GPIO10/SD3_18") (pintype "bidirectional"))
    )
    (net (code "53") (name "unconnected-(U6-GPIO11{slash}CMD-Pad19)") (class "Default")
      (node (ref "U6") (pin "19") (pinfunction "GPIO11/CMD_19") (pintype "bidirectional"))
    )
    (net (code "54") (name "unconnected-(U6-GPIO18{slash}CLK-Pad30)") (class "Default")
      (node (ref "U6") (pin "30") (pinfunction "GPIO18/CLK_30") (pintype "bidirectional"))
    )
    (net (code "55") (name "unconnected-(U6-GPIO21{slash}SDA-Pad33)") (class "Default")
      (node (ref "U6") (pin "33") (pinfunction "GPIO21/SDA_33") (pintype "bidirectional"))
    )
    (net (code "56") (name "unconnected-(U6-GPIO22{slash}SCL-Pad36)") (class "Default")
      (node (ref "U6") (pin "36") (pinfunction "GPIO22/SCL_36") (pintype "bidirectional"))
    )
    (net (code "57") (name "unconnected-(U6-GPIO23{slash}MOSI-Pad37)") (class "Default")
      (node (ref "U6") (pin "37") (pinfunction "GPIO23/MOSI_37") (pintype "bidirectional"))
    )
    (net (code "58") (name "unconnected-(U6-GPIO25{slash}ADC2CH8-Pad10)") (class "Default")
      (node (ref "U6") (pin "10") (pinfunction "GPIO25/ADC2CH8_10") (pintype "bidirectional"))
    )
    (net (code "59") (name "unconnected-(U6-GPIO26{slash}ADC2CH9-Pad11)") (class "Default")
      (node (ref "U6") (pin "11") (pinfunction "GPIO26/ADC2CH9_11") (pintype "bidirectional"))
    )
    (net (code "60") (name "unconnected-(U6-GPIO27{slash}ADC2CH7-Pad12)") (class "Default")
      (node (ref "U6") (pin "12") (pinfunction "GPIO27/ADC2CH7_12") (pintype "bidirectional"))
    )
    (net (code "61") (name "unconnected-(U6-GPIO34{slash}ADC1CH6-Pad6)") (class "Default")
      (node (ref "U6") (pin "6") (pinfunction "GPIO34/ADC1CH6_6") (pintype "bidirectional"))
    )
    (net (code "62") (name "unconnected-(U6-GPIO35{slash}ADC1CH7-Pad7)") (class "Default")
      (node (ref "U6") (pin "7") (pinfunction "GPIO35/ADC1CH7_7") (pintype "bidirectional"))
    )
    (net (code "63") (name "unconnected-(U6-GPIO36{slash}ADC1CH0{slash}SENSVP-Pad4)") (class "Default")
      (node (ref "U6") (pin "4") (pinfunction "GPIO36/ADC1CH0/SENSVP_4") (pintype "bidirectional"))
    )
    (net (code "64") (name "unconnected-(U6-GPIO39{slash}ADC1CH3{slash}SENSVN-Pad5)") (class "Default")
      (node (ref "U6") (pin "5") (pinfunction "GPIO39/ADC1CH3/SENSVN_5") (pintype "bidirectional"))
    )
  )
)
